# Sheet1.net
KiCad netlist of a schematic drawn in Altium Designer
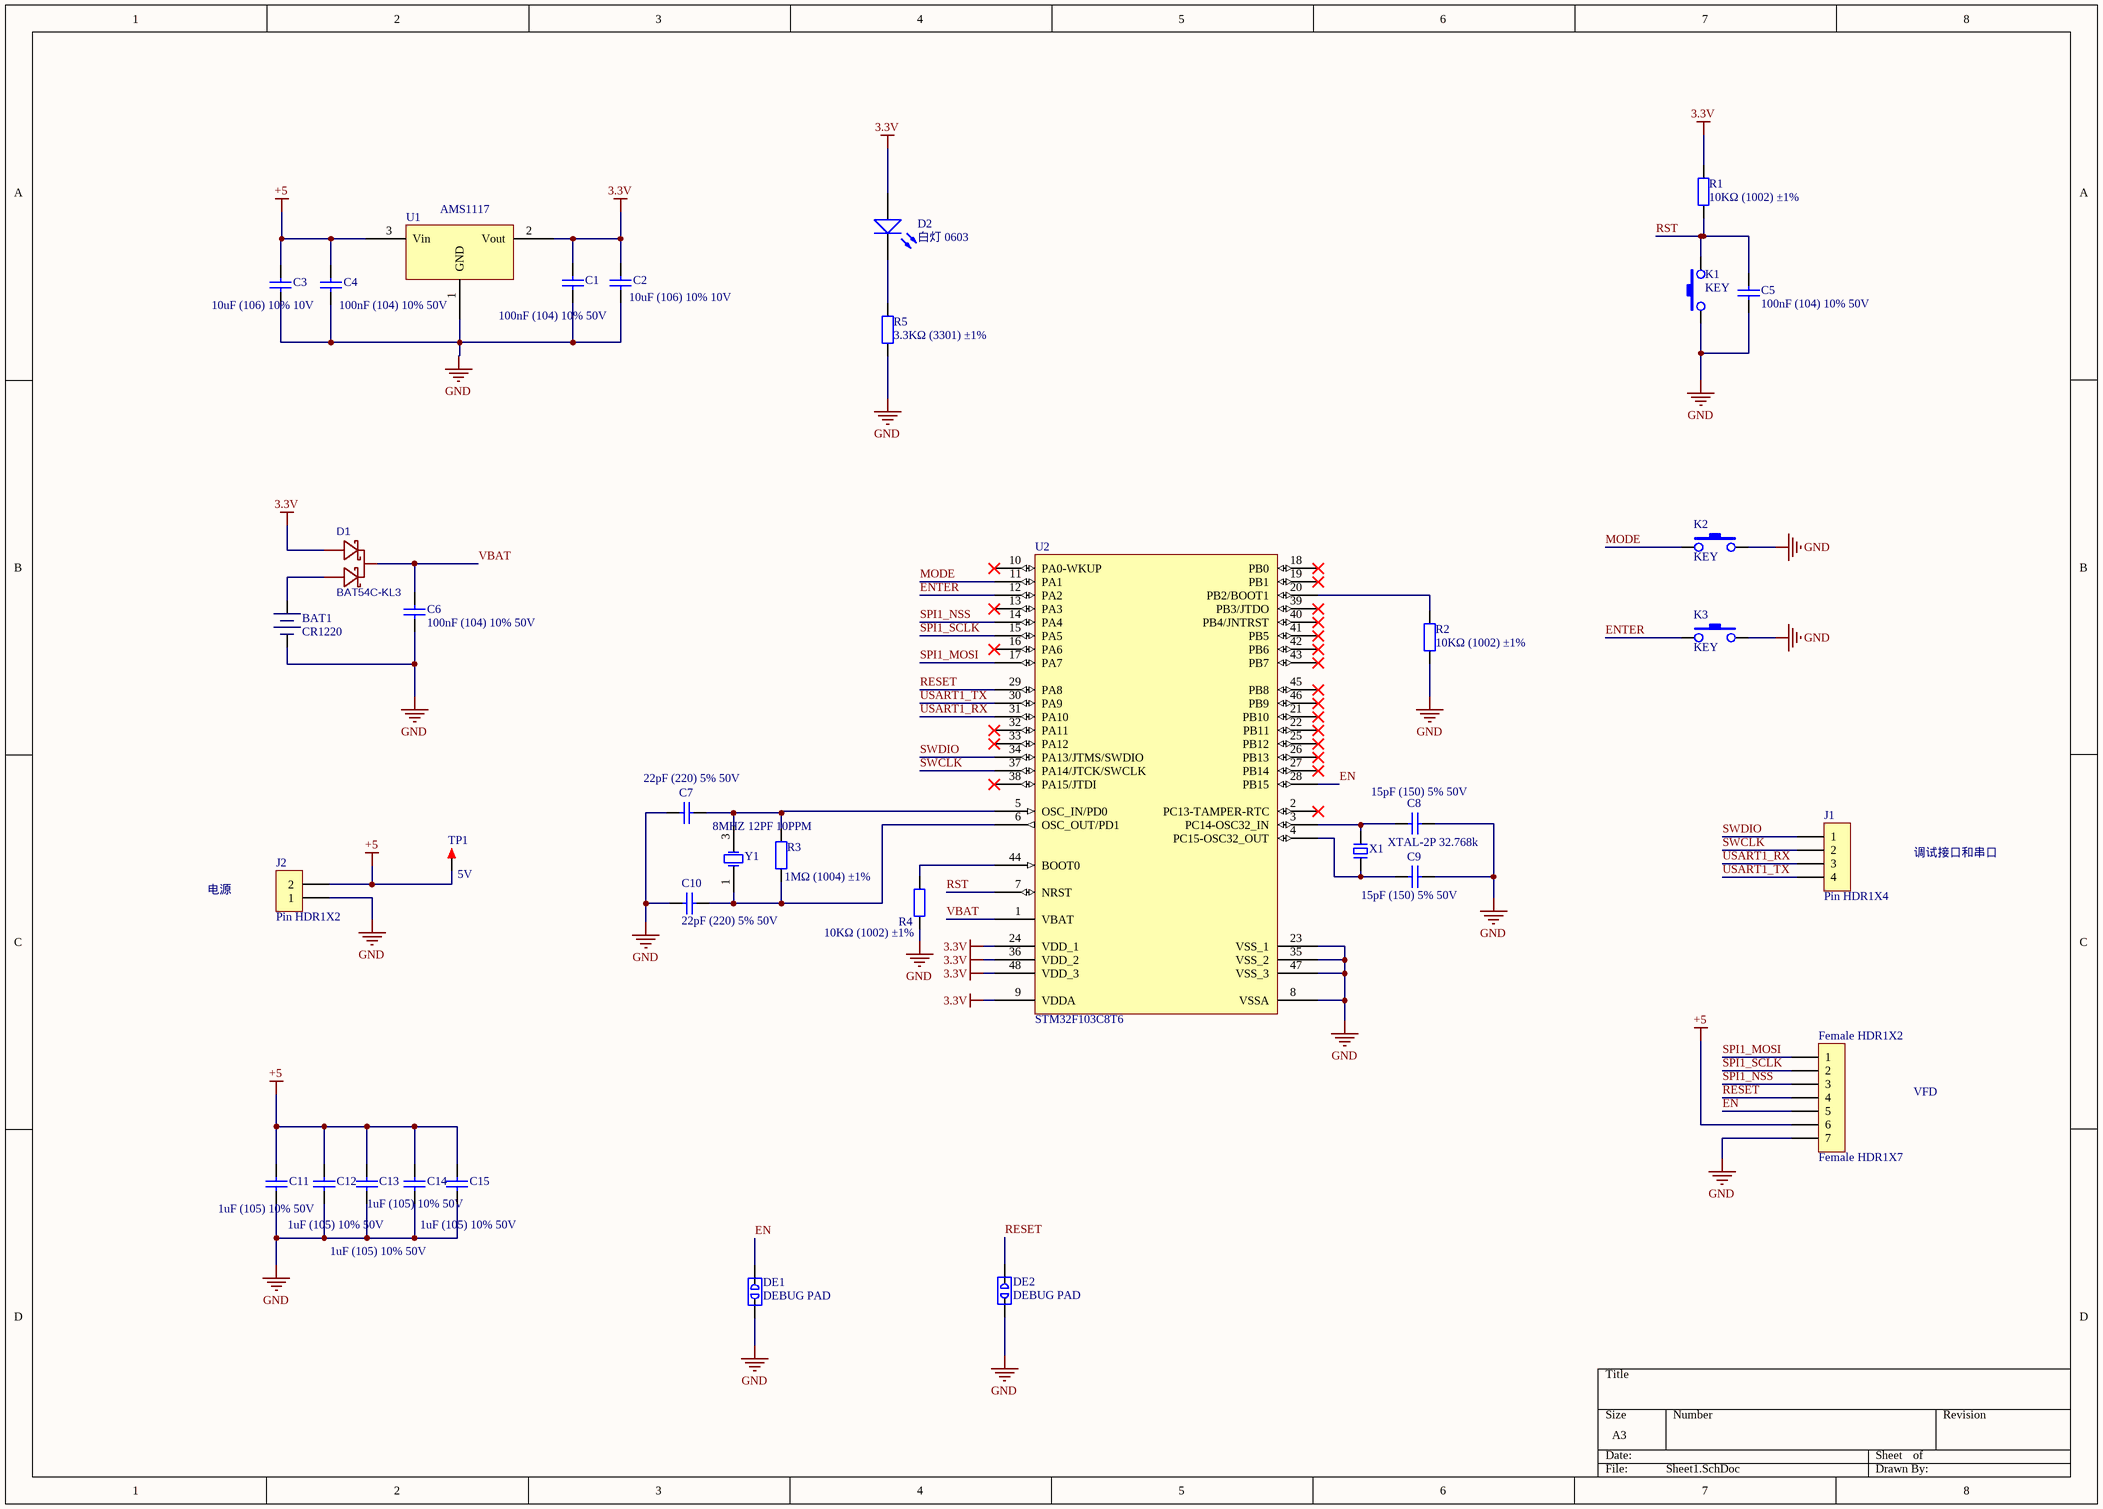
[diagram p0: Sheet1.SchDoc]

(export (version "E")
  (design (tool "Eeschema 10.0.6"))
  (components
    (comp (ref "BAT1") (value "CR1220") (footprint "CR1220-A") (libsource (lib "纽扣电池座") (part "CR1220")))
    (comp (ref "C1")
      (value "100nF (104) 10% 50V")
      (footprint "0603_C")
      (description "贴片电容")
      (libsource (lib "Miscellaneous Devices LC") (part "0603 100nF (104) 10% 50V"))
    )
    (comp (ref "C2")
      (value "10uF (106) 10% 10V")
      (footprint "0603_C")
      (description "贴片电容")
      (libsource (lib "Miscellaneous Devices LC") (part "0603 10uF (106) 10% 10V"))
    )
    (comp (ref "C3")
      (value "10uF (106) 10% 10V")
      (footprint "0603_C")
      (description "贴片电容")
      (libsource (lib "Miscellaneous Devices LC") (part "0603 10uF (106) 10% 10V"))
    )
    (comp (ref "C4")
      (value "100nF (104) 10% 50V")
      (footprint "0603_C")
      (description "贴片电容")
      (libsource (lib "Miscellaneous Devices LC") (part "0603 100nF (104) 10% 50V"))
    )
    (comp (ref "C5")
      (value "100nF (104) 10% 50V")
      (footprint "0603_C")
      (description "贴片电容")
      (libsource (lib "Miscellaneous Devices LC") (part "0603 100nF (104) 10% 50V"))
    )
    (comp (ref "C6")
      (value "100nF (104) 10% 50V")
      (footprint "0603_C")
      (description "贴片电容")
      (libsource (lib "Miscellaneous Devices LC") (part "0603 100nF (104) 10% 50V"))
    )
    (comp (ref "C7")
      (value "22pF (220) 5% 50V")
      (footprint "0603_C")
      (description "贴片电容")
      (libsource (lib "Miscellaneous Devices LC") (part "0603 22pF (220) 5% 50V"))
    )
    (comp (ref "C8")
      (value "15pF (150) 5% 50V")
      (footprint "0603_C")
      (description "贴片电容")
      (libsource (lib "Miscellaneous Devices LC") (part "0603 15pF (150) 5% 50V"))
    )
    (comp (ref "C9")
      (value "15pF (150) 5% 50V")
      (footprint "0603_C")
      (description "贴片电容")
      (libsource (lib "Miscellaneous Devices LC") (part "0603 15pF (150) 5% 50V"))
    )
    (comp (ref "C10")
      (value "22pF (220) 5% 50V")
      (footprint "0603_C")
      (description "贴片电容")
      (libsource (lib "Miscellaneous Devices LC") (part "0603 22pF (220) 5% 50V"))
    )
    (comp (ref "C11")
      (value "1uF (105) 10% 50V")
      (footprint "0603_C")
      (description "贴片电容")
      (libsource (lib "Miscellaneous Devices LC") (part "0603 1uF (105) 10% 50V"))
    )
    (comp (ref "C12")
      (value "1uF (105) 10% 50V")
      (footprint "0603_C")
      (description "贴片电容")
      (libsource (lib "Miscellaneous Devices LC") (part "0603 1uF (105) 10% 50V"))
    )
    (comp (ref "C13")
      (value "1uF (105) 10% 50V")
      (footprint "0603_C")
      (description "贴片电容")
      (libsource (lib "Miscellaneous Devices LC") (part "0603 1uF (105) 10% 50V"))
    )
    (comp (ref "C14")
      (value "1uF (105) 10% 50V")
      (footprint "0603_C")
      (description "贴片电容")
      (libsource (lib "Miscellaneous Devices LC") (part "0603 1uF (105) 10% 50V"))
    )
    (comp (ref "C15")
      (value "1uF (105) 10% 50V")
      (footprint "0603_C")
      (description "贴片电容")
      (libsource (lib "Miscellaneous Devices LC") (part "0603 1uF (105) 10% 50V"))
    )
    (comp (ref "D1")
      (value "BAT54C-KL3")
      (footprint "BAT54C_KL3")
      (fields (field (name "BOM_SUPPLIER PART") "C779698") (field (name "CONTRIBUTOR") "LCSC"))
      (libsource (lib "Schlib1") (part "BAT54C-KL3"))
    )
    (comp (ref "D2")
      (value "白灯 0603")
      (footprint "0603_LED_S1")
      (description "发光二极管")
      (libsource (lib "Miscellaneous Devices LC") (part "0603 白灯"))
    )
    (comp (ref "DE1")
      (value "DEBUG PAD")
      (footprint "DEBUG_A")
      (description "调试断点焊盘")
      (fields (field (name "版权归属") "源创客"))
      (libsource (lib "15.1 - 未分类器件") (part "DEBUG"))
    )
    (comp (ref "DE2")
      (value "DEBUG PAD")
      (footprint "DEBUG_A")
      (description "调试断点焊盘")
      (fields (field (name "版权归属") "源创客"))
      (libsource (lib "15.1 - 未分类器件") (part "DEBUG"))
    )
    (comp (ref "Female HDR1X2")
      (value "Female HDR1X7")
      (footprint "Fe-HDR1X7/2.54-S")
      (libsource (lib "排母") (part "Female HDR1X7"))
    )
    (comp (ref "J1")
      (value "Pin HDR1X4")
      (footprint "Pin HDR1X4/2.54mm-S")
      (libsource (lib "排针") (part "Pin HDR1X4"))
    )
    (comp (ref "J2")
      (value "Pin HDR1X2")
      (footprint "Pin HDR1X2/2.54mm-S")
      (libsource (lib "排针") (part "Pin HDR1X2"))
    )
    (comp (ref "K1") (value "KEY") (footprint "SMD-3X6X5") (libsource (lib "轻触开关") (part "KEY")))
    (comp (ref "K2") (value "KEY") (footprint "SMD-3X6X5") (libsource (lib "轻触开关") (part "KEY")))
    (comp (ref "K3") (value "KEY") (footprint "SMD-3X6X5") (libsource (lib "轻触开关") (part "KEY")))
    (comp (ref "R1")
      (value "10KΩ (1002) ±1%")
      (footprint "0603_R")
      (description "贴片电阻")
      (libsource (lib "Miscellaneous Devices LC") (part "0603 10KΩ (1002) 1%"))
    )
    (comp (ref "R2")
      (value "10KΩ (1002) ±1%")
      (footprint "0603_R")
      (description "贴片电阻")
      (libsource (lib "") (part "0603 10KΩ (1002) 1%_1"))
    )
    (comp (ref "R3")
      (value "1MΩ (1004) ±1%")
      (footprint "0603_R")
      (description "贴片电阻")
      (libsource (lib "Miscellaneous Devices LC") (part "0603 1MΩ (1004) 1%"))
    )
    (comp (ref "R4")
      (value "10KΩ (1002) ±1%")
      (footprint "0603_R")
      (description "贴片电阻")
      (libsource (lib "Miscellaneous Devices LC") (part "0603 10KΩ (1002) 1%"))
    )
    (comp (ref "R5")
      (value "3.3KΩ (3301) ±1%")
      (footprint "0603_R")
      (description "贴片电阻")
      (libsource (lib "Miscellaneous Devices LC") (part "0603 3.3KΩ (3301) 1%"))
    )
    (comp (ref "TP1")
      (value "5V")
      (footprint "TEST 1")
      (description "测试点")
      (fields (field (name "版权归属") "源创客"))
      (libsource (lib "15.1 - 未分类器件") (part "TEST"))
    )
    (comp (ref "U1")
      (value "AMS1117")
      (footprint "SOT223")
      (description "三端稳压芯片")
      (libsource (lib "电源芯片") (part "AMS1117"))
    )
    (comp (ref "U2")
      (value "STM32F103C8T6")
      (footprint "LQFP48 7X7")
      (libsource (lib "STM32系列") (part "STM32F103C8T6"))
    )
    (comp (ref "X1")
      (value "XTAL-2P 32.768k")
      (footprint "OSC 455E-LI")
      (description "2脚无源脚晶振")
      (libsource (lib "晶振") (part "XTAL-2P"))
    )
    (comp (ref "Y1")
      (value "8MHZ 12PF 10PPM")
      (footprint "SMD-3225_4P")
      (description "贴片晶振")
      (libsource (lib "Miscellaneous Devices LC") (part "SMD-3225_4P  25MHZ 12PF 10PPM"))
    )
  )
  (nets
    (net (code "1") (name "+5") (class "Default")
      (node (ref "C11") (pin "2") (pinfunction "2_2") (pintype "passive"))
      (node (ref "C12") (pin "2") (pinfunction "2_2") (pintype "passive"))
      (node (ref "C13") (pin "2") (pinfunction "2_2") (pintype "passive"))
      (node (ref "C14") (pin "2") (pinfunction "2_2") (pintype "passive"))
      (node (ref "C15") (pin "2") (pinfunction "2_2") (pintype "passive"))
      (node (ref "C3") (pin "2") (pinfunction "2_2") (pintype "passive"))
      (node (ref "C4") (pin "2") (pinfunction "2_2") (pintype "passive"))
      (node (ref "Female HDR1X2") (pin "6") (pinfunction "6_6") (pintype "passive"))
      (node (ref "J2") (pin "2") (pinfunction "2_2") (pintype "passive"))
      (node (ref "TP1") (pin "1") (pinfunction "1_1") (pintype "passive"))
      (node (ref "U1") (pin "3") (pinfunction "Vin_3") (pintype "passive"))
    )
    (net (code "2") (name "/EN") (class "Default")
      (node (ref "DE1") (pin "2") (pinfunction "2_2") (pintype "passive"))
      (node (ref "Female HDR1X2") (pin "5") (pinfunction "5_5") (pintype "passive"))
      (node (ref "U2") (pin "28") (pinfunction "PB15_28") (pintype "bidirectional"))
    )
    (net (code "3") (name "/ENTER") (class "Default")
      (node (ref "K3") (pin "1") (pinfunction "1_1") (pintype "passive"))
      (node (ref "U2") (pin "12") (pinfunction "PA2_12") (pintype "bidirectional"))
    )
    (net (code "4") (name "/MODE") (class "Default")
      (node (ref "K2") (pin "1") (pinfunction "1_1") (pintype "passive"))
      (node (ref "U2") (pin "11") (pinfunction "PA1_11") (pintype "bidirectional"))
    )
    (net (code "5") (name "/RESET") (class "Default")
      (node (ref "DE2") (pin "2") (pinfunction "2_2") (pintype "passive"))
      (node (ref "Female HDR1X2") (pin "4") (pinfunction "4_4") (pintype "passive"))
      (node (ref "U2") (pin "29") (pinfunction "PA8_29") (pintype "bidirectional"))
    )
    (net (code "6") (name "/RST") (class "Default")
      (node (ref "C5") (pin "2") (pinfunction "2_2") (pintype "passive"))
      (node (ref "K1") (pin "3") (pinfunction "3_3") (pintype "passive"))
      (node (ref "R1") (pin "1") (pinfunction "1_1") (pintype "passive"))
      (node (ref "U2") (pin "7") (pinfunction "NRST_7") (pintype "bidirectional"))
    )
    (net (code "7") (name "/SPI1_MOSI") (class "Default")
      (node (ref "Female HDR1X2") (pin "1") (pinfunction "1_1") (pintype "passive"))
      (node (ref "U2") (pin "17") (pinfunction "PA7_17") (pintype "bidirectional"))
    )
    (net (code "8") (name "/SPI1_NSS") (class "Default")
      (node (ref "Female HDR1X2") (pin "3") (pinfunction "3_3") (pintype "passive"))
      (node (ref "U2") (pin "14") (pinfunction "PA4_14") (pintype "bidirectional"))
    )
    (net (code "9") (name "/SPI1_SCLK") (class "Default")
      (node (ref "Female HDR1X2") (pin "2") (pinfunction "2_2") (pintype "passive"))
      (node (ref "U2") (pin "15") (pinfunction "PA5_15") (pintype "bidirectional"))
    )
    (net (code "10") (name "/SWCLK") (class "Default")
      (node (ref "J1") (pin "2") (pinfunction "2_2") (pintype "passive"))
      (node (ref "U2") (pin "37") (pinfunction "PA14/JTCK/SWCLK_37") (pintype "bidirectional"))
    )
    (net (code "11") (name "/SWDIO") (class "Default")
      (node (ref "J1") (pin "1") (pinfunction "1_1") (pintype "passive"))
      (node (ref "U2") (pin "34") (pinfunction "PA13/JTMS/SWDIO_34") (pintype "bidirectional"))
    )
    (net (code "12") (name "/USART1_RX") (class "Default")
      (node (ref "J1") (pin "3") (pinfunction "3_3") (pintype "passive"))
      (node (ref "U2") (pin "31") (pinfunction "PA10_31") (pintype "bidirectional"))
    )
    (net (code "13") (name "/USART1_TX") (class "Default")
      (node (ref "J1") (pin "4") (pinfunction "4_4") (pintype "passive"))
      (node (ref "U2") (pin "30") (pinfunction "PA9_30") (pintype "bidirectional"))
    )
    (net (code "14") (name "/VBAT") (class "Default")
      (node (ref "C6") (pin "2") (pinfunction "2_2") (pintype "passive"))
      (node (ref "D1") (pin "3") (pinfunction "K_3") (pintype "passive"))
      (node (ref "U2") (pin "1") (pinfunction "VBAT_1") (pintype "power_in"))
    )
    (net (code "15") (name "3.3V") (class "Default")
      (node (ref "C1") (pin "2") (pinfunction "2_2") (pintype "passive"))
      (node (ref "C2") (pin "2") (pinfunction "2_2") (pintype "passive"))
      (node (ref "D1") (pin "1") (pinfunction "A_1") (pintype "passive"))
      (node (ref "D2") (pin "A") (pinfunction "A_A") (pintype "passive"))
      (node (ref "R1") (pin "2") (pinfunction "2_2") (pintype "passive"))
      (node (ref "U1") (pin "2") (pinfunction "Vout_2") (pintype "passive"))
      (node (ref "U2") (pin "24") (pinfunction "VDD_1_24") (pintype "power_in"))
      (node (ref "U2") (pin "36") (pinfunction "VDD_2_36") (pintype "power_in"))
      (node (ref "U2") (pin "48") (pinfunction "VDD_3_48") (pintype "power_in"))
      (node (ref "U2") (pin "9") (pinfunction "VDDA_9") (pintype "power_in"))
    )
    (net (code "16") (name "GND") (class "Default")
      (node (ref "BAT1") (pin "2") (pinfunction "2_2") (pintype "passive"))
      (node (ref "C1") (pin "1") (pinfunction "1_1") (pintype "passive"))
      (node (ref "C10") (pin "1") (pinfunction "1_1") (pintype "passive"))
      (node (ref "C11") (pin "1") (pinfunction "1_1") (pintype "passive"))
      (node (ref "C12") (pin "1") (pinfunction "1_1") (pintype "passive"))
      (node (ref "C13") (pin "1") (pinfunction "1_1") (pintype "passive"))
      (node (ref "C14") (pin "1") (pinfunction "1_1") (pintype "passive"))
      (node (ref "C15") (pin "1") (pinfunction "1_1") (pintype "passive"))
      (node (ref "C2") (pin "1") (pinfunction "1_1") (pintype "passive"))
      (node (ref "C3") (pin "1") (pinfunction "1_1") (pintype "passive"))
      (node (ref "C4") (pin "1") (pinfunction "1_1") (pintype "passive"))
      (node (ref "C5") (pin "1") (pinfunction "1_1") (pintype "passive"))
      (node (ref "C6") (pin "1") (pinfunction "1_1") (pintype "passive"))
      (node (ref "C7") (pin "1") (pinfunction "1_1") (pintype "passive"))
      (node (ref "C8") (pin "2") (pinfunction "2_2") (pintype "passive"))
      (node (ref "C9") (pin "2") (pinfunction "2_2") (pintype "passive"))
      (node (ref "DE1") (pin "1") (pinfunction "1_1") (pintype "passive"))
      (node (ref "DE2") (pin "1") (pinfunction "1_1") (pintype "passive"))
      (node (ref "Female HDR1X2") (pin "7") (pinfunction "7_7") (pintype "passive"))
      (node (ref "J2") (pin "1") (pinfunction "1_1") (pintype "passive"))
      (node (ref "K1") (pin "1") (pinfunction "1_1") (pintype "passive"))
      (node (ref "K2") (pin "3") (pinfunction "3_3") (pintype "passive"))
      (node (ref "K3") (pin "3") (pinfunction "3_3") (pintype "passive"))
      (node (ref "R2") (pin "2") (pinfunction "2_2") (pintype "passive"))
      (node (ref "R4") (pin "1") (pinfunction "1_1") (pintype "passive"))
      (node (ref "R5") (pin "1") (pinfunction "1_1") (pintype "passive"))
      (node (ref "U1") (pin "1") (pinfunction "GND_1") (pintype "passive"))
      (node (ref "U2") (pin "23") (pinfunction "VSS_1_23") (pintype "power_in"))
      (node (ref "U2") (pin "35") (pinfunction "VSS_2_35") (pintype "power_in"))
      (node (ref "U2") (pin "47") (pinfunction "VSS_3_47") (pintype "power_in"))
      (node (ref "U2") (pin "8") (pinfunction "VSSA_8") (pintype "power_in"))
    )
    (net (code "17") (name "Net-(BAT1-Pad1)") (class "Default")
      (node (ref "BAT1") (pin "1") (pinfunction "1_1") (pintype "passive"))
      (node (ref "D1") (pin "2") (pinfunction "A_2") (pintype "passive"))
    )
    (net (code "18") (name "Net-(D2-PadK)") (class "Default")
      (node (ref "D2") (pin "K") (pinfunction "K_K") (pintype "passive"))
      (node (ref "R5") (pin "2") (pinfunction "2_2") (pintype "passive"))
    )
    (net (code "19") (name "Net-(U2-BOOT0)") (class "Default")
      (node (ref "R4") (pin "2") (pinfunction "2_2") (pintype "passive"))
      (node (ref "U2") (pin "44") (pinfunction "BOOT0_44") (pintype "input"))
    )
    (net (code "20") (name "Net-(U2-OSC_IN{slash}PD0)") (class "Default")
      (node (ref "C7") (pin "2") (pinfunction "2_2") (pintype "passive"))
      (node (ref "R3") (pin "2") (pinfunction "2_2") (pintype "passive"))
      (node (ref "U2") (pin "5") (pinfunction "OSC_IN/PD0_5") (pintype "input"))
      (node (ref "Y1") (pin "3") (pinfunction "OSC2_3") (pintype "passive"))
    )
    (net (code "21") (name "Net-(U2-OSC_OUT{slash}PD1)") (class "Default")
      (node (ref "C10") (pin "2") (pinfunction "2_2") (pintype "passive"))
      (node (ref "R3") (pin "1") (pinfunction "1_1") (pintype "passive"))
      (node (ref "U2") (pin "6") (pinfunction "OSC_OUT/PD1_6") (pintype "output"))
      (node (ref "Y1") (pin "1") (pinfunction "OSC1_1") (pintype "passive"))
    )
    (net (code "22") (name "Net-(U2-PB2{slash}BOOT1)") (class "Default")
      (node (ref "R2") (pin "1") (pinfunction "1_1") (pintype "passive"))
      (node (ref "U2") (pin "20") (pinfunction "PB2/BOOT1_20") (pintype "bidirectional"))
    )
    (net (code "23") (name "Net-(U2-PC14-OSC32_IN)") (class "Default")
      (node (ref "C8") (pin "1") (pinfunction "1_1") (pintype "passive"))
      (node (ref "U2") (pin "3") (pinfunction "PC14-OSC32_IN_3") (pintype "bidirectional"))
      (node (ref "X1") (pin "2") (pinfunction "2_2") (pintype "passive"))
    )
    (net (code "24") (name "Net-(U2-PC15-OSC32_OUT)") (class "Default")
      (node (ref "C9") (pin "1") (pinfunction "1_1") (pintype "passive"))
      (node (ref "U2") (pin "4") (pinfunction "PC15-OSC32_OUT_4") (pintype "bidirectional"))
      (node (ref "X1") (pin "1") (pinfunction "1_1") (pintype "passive"))
    )
    (net (code "25") (name "unconnected-(U2-PA0-WKUP-Pad10)") (class "Default")
      (node (ref "U2") (pin "10") (pinfunction "PA0-WKUP_10") (pintype "bidirectional+no_connect"))
    )
    (net (code "26") (name "unconnected-(U2-PA3-Pad13)") (class "Default")
      (node (ref "U2") (pin "13") (pinfunction "PA3_13") (pintype "bidirectional+no_connect"))
    )
    (net (code "27") (name "unconnected-(U2-PA6-Pad16)") (class "Default")
      (node (ref "U2") (pin "16") (pinfunction "PA6_16") (pintype "bidirectional+no_connect"))
    )
    (net (code "28") (name "unconnected-(U2-PA11-Pad32)") (class "Default")
      (node (ref "U2") (pin "32") (pinfunction "PA11_32") (pintype "bidirectional+no_connect"))
    )
    (net (code "29") (name "unconnected-(U2-PA12-Pad33)") (class "Default")
      (node (ref "U2") (pin "33") (pinfunction "PA12_33") (pintype "bidirectional+no_connect"))
    )
    (net (code "30") (name "unconnected-(U2-PA15{slash}JTDI-Pad38)") (class "Default")
      (node (ref "U2") (pin "38") (pinfunction "PA15/JTDI_38") (pintype "bidirectional+no_connect"))
    )
    (net (code "31") (name "unconnected-(U2-PB0-Pad18)") (class "Default")
      (node (ref "U2") (pin "18") (pinfunction "PB0_18") (pintype "bidirectional+no_connect"))
    )
    (net (code "32") (name "unconnected-(U2-PB1-Pad19)") (class "Default")
      (node (ref "U2") (pin "19") (pinfunction "PB1_19") (pintype "bidirectional+no_connect"))
    )
    (net (code "33") (name "unconnected-(U2-PB3{slash}JTDO-Pad39)") (class "Default")
      (node (ref "U2") (pin "39") (pinfunction "PB3/JTDO_39") (pintype "bidirectional+no_connect"))
    )
    (net (code "34") (name "unconnected-(U2-PB4{slash}JNTRST-Pad40)") (class "Default")
      (node (ref "U2") (pin "40") (pinfunction "PB4/JNTRST_40") (pintype "bidirectional+no_connect"))
    )
    (net (code "35") (name "unconnected-(U2-PB5-Pad41)") (class "Default")
      (node (ref "U2") (pin "41") (pinfunction "PB5_41") (pintype "bidirectional+no_connect"))
    )
    (net (code "36") (name "unconnected-(U2-PB6-Pad42)") (class "Default")
      (node (ref "U2") (pin "42") (pinfunction "PB6_42") (pintype "bidirectional+no_connect"))
    )
    (net (code "37") (name "unconnected-(U2-PB7-Pad43)") (class "Default")
      (node (ref "U2") (pin "43") (pinfunction "PB7_43") (pintype "bidirectional+no_connect"))
    )
    (net (code "38") (name "unconnected-(U2-PB8-Pad45)") (class "Default")
      (node (ref "U2") (pin "45") (pinfunction "PB8_45") (pintype "bidirectional+no_connect"))
    )
    (net (code "39") (name "unconnected-(U2-PB9-Pad46)") (class "Default")
      (node (ref "U2") (pin "46") (pinfunction "PB9_46") (pintype "bidirectional+no_connect"))
    )
    (net (code "40") (name "unconnected-(U2-PB10-Pad21)") (class "Default")
      (node (ref "U2") (pin "21") (pinfunction "PB10_21") (pintype "bidirectional+no_connect"))
    )
    (net (code "41") (name "unconnected-(U2-PB11-Pad22)") (class "Default")
      (node (ref "U2") (pin "22") (pinfunction "PB11_22") (pintype "bidirectional+no_connect"))
    )
    (net (code "42") (name "unconnected-(U2-PB12-Pad25)") (class "Default")
      (node (ref "U2") (pin "25") (pinfunction "PB12_25") (pintype "bidirectional+no_connect"))
    )
    (net (code "43") (name "unconnected-(U2-PB13-Pad26)") (class "Default")
      (node (ref "U2") (pin "26") (pinfunction "PB13_26") (pintype "bidirectional+no_connect"))
    )
    (net (code "44") (name "unconnected-(U2-PB14-Pad27)") (class "Default")
      (node (ref "U2") (pin "27") (pinfunction "PB14_27") (pintype "bidirectional+no_connect"))
    )
    (net (code "45") (name "unconnected-(U2-PC13-TAMPER-RTC-Pad2)") (class "Default")
      (node (ref "U2") (pin "2") (pinfunction "PC13-TAMPER-RTC_2") (pintype "bidirectional+no_connect"))
    )
  )
)
